# thermometer_main.net
KiCad netlist of a schematic drawn in EAGLE
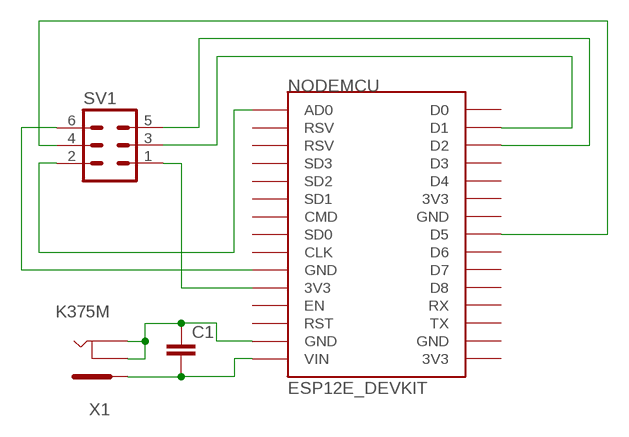
[diagram p0: schematic, sheet 1]

(export (version "E")
  (design (tool "Eeschema 10.0.6"))
  (components
    (comp (ref "C1")
      (value "C-EU025-025X050")
      (footprint "eagle-import:C025-025X050")
      (libsource (lib "eagle-import") (part "C-EU025-025X050"))
    )
    (comp (ref "NODEMCU")
      (value "ESP12E_DEVKIT")
      (footprint "eagle-import:ESP12E_DEVKIT")
      (libsource (lib "eagle-import") (part "ESP12E_DEVKIT"))
    )
    (comp (ref "SV1")
      (value "ML6L")
      (footprint "eagle-import:ML6L")
      (libsource (lib "eagle-import") (part "ML6L"))
    )
    (comp (ref "X1")
      (value "K375M")
      (footprint "eagle-import:K375M")
      (libsource (lib "eagle-import") (part "K375M"))
    )
  )
  (nets
    (net (code "1") (name "Net-(C1-Pad1)") (class "Default")
      (node (ref "C1") (pin "1") (pinfunction "1_1") (pintype "passive"))
      (node (ref "NODEMCU") (pin "GND@1") (pinfunction "GND_GND@1") (pintype "bidirectional"))
      (node (ref "X1") (pin "2") (pinfunction "2_2") (pintype "passive"))
      (node (ref "X1") (pin "3") (pinfunction "3_3") (pintype "passive"))
    )
    (net (code "2") (name "Net-(C1-Pad2)") (class "Default")
      (node (ref "C1") (pin "2") (pinfunction "2_2") (pintype "passive"))
      (node (ref "NODEMCU") (pin "VIN") (pinfunction "VIN_VIN") (pintype "bidirectional"))
      (node (ref "X1") (pin "1") (pinfunction "1_1") (pintype "passive"))
    )
    (net (code "3") (name "Net-(NODEMCU-3V3-Pad3V3@0)") (class "Default")
      (node (ref "NODEMCU") (pin "3V3@0") (pinfunction "3V3_3V3@0") (pintype "bidirectional"))
      (node (ref "SV1") (pin "1") (pinfunction "1_1") (pintype "passive"))
    )
    (net (code "4") (name "Net-(NODEMCU-GND-PadGND@0)") (class "Default")
      (node (ref "NODEMCU") (pin "GND@0") (pinfunction "GND_GND@0") (pintype "bidirectional"))
      (node (ref "SV1") (pin "6") (pinfunction "6_6") (pintype "passive"))
    )
    (net (code "5") (name "Net-(NODEMCU-PadAD0)") (class "Default")
      (node (ref "NODEMCU") (pin "AD0") (pinfunction "AD0_AD0") (pintype "bidirectional"))
      (node (ref "SV1") (pin "2") (pinfunction "2_2") (pintype "passive"))
    )
    (net (code "6") (name "Net-(NODEMCU-PadD1)") (class "Default")
      (node (ref "NODEMCU") (pin "D1") (pinfunction "D1_D1") (pintype "bidirectional"))
      (node (ref "SV1") (pin "3") (pinfunction "3_3") (pintype "passive"))
    )
    (net (code "7") (name "Net-(NODEMCU-PadD2)") (class "Default")
      (node (ref "NODEMCU") (pin "D2") (pinfunction "D2_D2") (pintype "bidirectional"))
      (node (ref "SV1") (pin "5") (pinfunction "5_5") (pintype "passive"))
    )
    (net (code "8") (name "Net-(NODEMCU-PadD5)") (class "Default")
      (node (ref "NODEMCU") (pin "D5") (pinfunction "D5_D5") (pintype "bidirectional"))
      (node (ref "SV1") (pin "4") (pinfunction "4_4") (pintype "passive"))
    )
    (net (code "9") (name "unconnected-(NODEMCU-3V3-Pad3V3@1)") (class "Default")
      (node (ref "NODEMCU") (pin "3V3@1") (pinfunction "3V3_3V3@1") (pintype "bidirectional"))
    )
    (net (code "10") (name "unconnected-(NODEMCU-3V3-Pad3V3@2)") (class "Default")
      (node (ref "NODEMCU") (pin "3V3@2") (pinfunction "3V3_3V3@2") (pintype "bidirectional"))
    )
    (net (code "11") (name "unconnected-(NODEMCU-GND-PadGND@2)") (class "Default")
      (node (ref "NODEMCU") (pin "GND@2") (pinfunction "GND_GND@2") (pintype "bidirectional"))
    )
    (net (code "12") (name "unconnected-(NODEMCU-GND-PadGND@3)") (class "Default")
      (node (ref "NODEMCU") (pin "GND@3") (pinfunction "GND_GND@3") (pintype "bidirectional"))
    )
    (net (code "13") (name "unconnected-(NODEMCU-PadCLK)") (class "Default")
      (node (ref "NODEMCU") (pin "CLK") (pinfunction "CLK_CLK") (pintype "bidirectional"))
    )
    (net (code "14") (name "unconnected-(NODEMCU-PadCMD)") (class "Default")
      (node (ref "NODEMCU") (pin "CMD") (pinfunction "CMD_CMD") (pintype "bidirectional"))
    )
    (net (code "15") (name "unconnected-(NODEMCU-PadD0)") (class "Default")
      (node (ref "NODEMCU") (pin "D0") (pinfunction "D0_D0") (pintype "bidirectional"))
    )
    (net (code "16") (name "unconnected-(NODEMCU-PadD3)") (class "Default")
      (node (ref "NODEMCU") (pin "D3") (pinfunction "D3_D3") (pintype "bidirectional"))
    )
    (net (code "17") (name "unconnected-(NODEMCU-PadD4)") (class "Default")
      (node (ref "NODEMCU") (pin "D4") (pinfunction "D4_D4") (pintype "bidirectional"))
    )
    (net (code "18") (name "unconnected-(NODEMCU-PadD6)") (class "Default")
      (node (ref "NODEMCU") (pin "D6") (pinfunction "D6_D6") (pintype "bidirectional"))
    )
    (net (code "19") (name "unconnected-(NODEMCU-PadD7)") (class "Default")
      (node (ref "NODEMCU") (pin "D7") (pinfunction "D7_D7") (pintype "bidirectional"))
    )
    (net (code "20") (name "unconnected-(NODEMCU-PadD8)") (class "Default")
      (node (ref "NODEMCU") (pin "D8") (pinfunction "D8_D8") (pintype "bidirectional"))
    )
    (net (code "21") (name "unconnected-(NODEMCU-PadEN)") (class "Default")
      (node (ref "NODEMCU") (pin "EN") (pinfunction "EN_EN") (pintype "bidirectional"))
    )
    (net (code "22") (name "unconnected-(NODEMCU-PadRST)") (class "Default")
      (node (ref "NODEMCU") (pin "RST") (pinfunction "RST_RST") (pintype "bidirectional"))
    )
    (net (code "23") (name "unconnected-(NODEMCU-PadRX)") (class "Default")
      (node (ref "NODEMCU") (pin "RX") (pinfunction "RX_RX") (pintype "bidirectional"))
    )
    (net (code "24") (name "unconnected-(NODEMCU-PadSD0)") (class "Default")
      (node (ref "NODEMCU") (pin "SD0") (pinfunction "SD0_SD0") (pintype "bidirectional"))
    )
    (net (code "25") (name "unconnected-(NODEMCU-PadSD1)") (class "Default")
      (node (ref "NODEMCU") (pin "SD1") (pinfunction "SD1_SD1") (pintype "bidirectional"))
    )
    (net (code "26") (name "unconnected-(NODEMCU-PadSD2)") (class "Default")
      (node (ref "NODEMCU") (pin "SD2") (pinfunction "SD2_SD2") (pintype "bidirectional"))
    )
    (net (code "27") (name "unconnected-(NODEMCU-PadSD3)") (class "Default")
      (node (ref "NODEMCU") (pin "SD3") (pinfunction "SD3_SD3") (pintype "bidirectional"))
    )
    (net (code "28") (name "unconnected-(NODEMCU-PadTX)") (class "Default")
      (node (ref "NODEMCU") (pin "TX") (pinfunction "TX_TX") (pintype "bidirectional"))
    )
    (net (code "29") (name "unconnected-(NODEMCU-RSV-PadRSV@0)") (class "Default")
      (node (ref "NODEMCU") (pin "RSV@0") (pinfunction "RSV_RSV@0") (pintype "bidirectional"))
    )
    (net (code "30") (name "unconnected-(NODEMCU-RSV-PadRSV@1)") (class "Default")
      (node (ref "NODEMCU") (pin "RSV@1") (pinfunction "RSV_RSV@1") (pintype "bidirectional"))
    )
  )
)
